# ME433_Spring2017.net
KiCad netlist of a schematic drawn in EAGLE
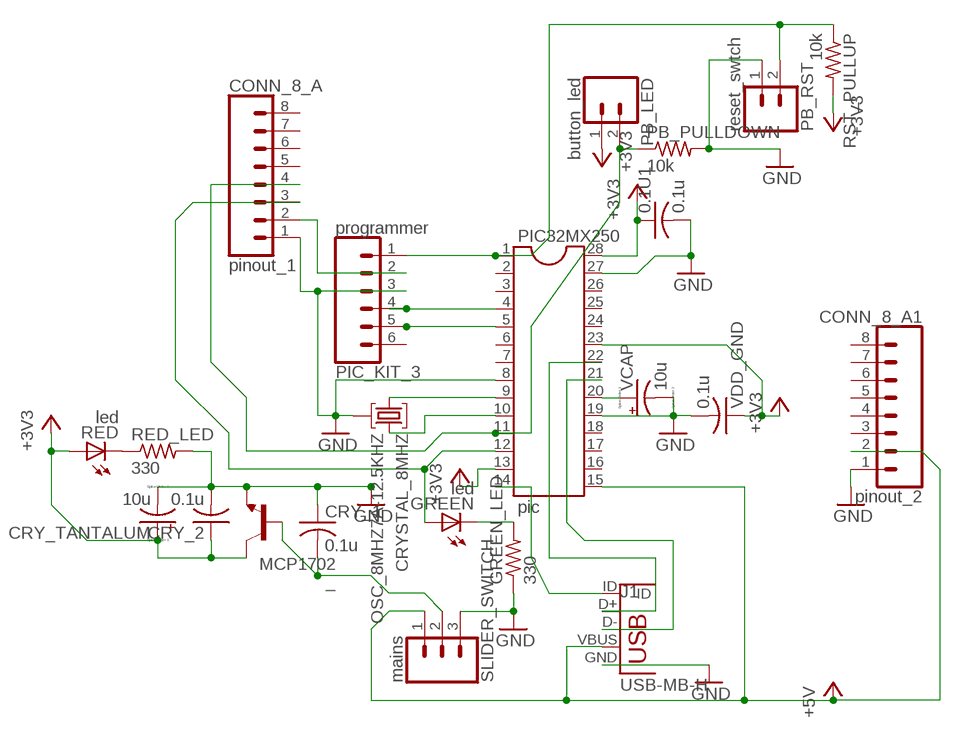
[diagram p0: schematic, sheet 1]

(export (version "E")
  (design (tool "Eeschema 10.0.6"))
  (components
    (comp (ref "0.1U1")
      (value "0.1u")
      (footprint "eagle-import:C025-025X050")
      (libsource (lib "eagle-import") (part "C-US025-025X050"))
    )
    (comp (ref "CONN_8_A")
      (value "pinout_1")
      (footprint "eagle-import:1X08")
      (libsource (lib "eagle-import") (part "CONN_08{dblquote}"))
    )
    (comp (ref "CONN_8_A1")
      (value "pinout_2")
      (footprint "eagle-import:1X08")
      (libsource (lib "eagle-import") (part "CONN_08{dblquote}"))
    )
    (comp (ref "CRYSTAL_8MHZ")
      (value "OSC_8MHZ7A-12.5KHZ")
      (footprint "eagle-import:HC49U")
      (libsource (lib "eagle-import") (part "OSC_8MHZ7A-12.5KHZ"))
    )
    (comp (ref "CRY_1")
      (value "0.1u")
      (footprint "eagle-import:C025-025X050")
      (libsource (lib "eagle-import") (part "C-US025-025X050"))
    )
    (comp (ref "CRY_2")
      (value "0.1u")
      (footprint "eagle-import:C025-025X050")
      (libsource (lib "eagle-import") (part "C-US025-025X050"))
    )
    (comp (ref "CRY_TANTALUM")
      (value "10u")
      (footprint "eagle-import:B45181B")
      (libsource (lib "eagle-import") (part "CPOL-USB45181B"))
    )
    (comp (ref "GREEN")
      (value "led")
      (footprint "eagle-import:SFH482")
      (libsource (lib "eagle-import") (part "LEDSFH482"))
    )
    (comp (ref "GREEN_LED")
      (value "330")
      (footprint "eagle-import:0204_7")
      (libsource (lib "eagle-import") (part "R-US_0204/7"))
    )
    (comp (ref "J1")
      (value "USB-MB-H")
      (footprint "eagle-import:USB-MB-H")
      (libsource (lib "eagle-import") (part "USB-MB-H"))
    )
    (comp (ref "PB_LED")
      (value "button_led")
      (footprint "eagle-import:BUTTONS")
      (libsource (lib "eagle-import") (part "BUTTONS"))
    )
    (comp (ref "PB_PULLDOWN")
      (value "10k")
      (footprint "eagle-import:0204_7")
      (libsource (lib "eagle-import") (part "R-US_0204/7"))
    )
    (comp (ref "PB_RST")
      (value "reset_swtch")
      (footprint "eagle-import:BUTTONS")
      (libsource (lib "eagle-import") (part "BUTTONS"))
    )
    (comp (ref "PIC32MX250")
      (value "pic")
      (footprint "eagle-import:PIC")
      (libsource (lib "eagle-import") (part "PIC-3"))
    )
    (comp (ref "PIC_KIT_3")
      (value "programmer")
      (footprint "eagle-import:1X06_NO_SILK")
      (libsource (lib "eagle-import") (part "PICKIT3NO_SILK_FEMALE_PTH"))
    )
    (comp (ref "RED")
      (value "led")
      (footprint "eagle-import:SFH482")
      (libsource (lib "eagle-import") (part "LEDSFH482"))
    )
    (comp (ref "RED_LED")
      (value "330")
      (footprint "eagle-import:0204_7")
      (libsource (lib "eagle-import") (part "R-US_0204/7"))
    )
    (comp (ref "RST_PULLUP")
      (value "10k")
      (footprint "eagle-import:0204_7")
      (libsource (lib "eagle-import") (part "R-US_0204/7"))
    )
    (comp (ref "SLIDER_SWITCH")
      (value "mains")
      (footprint "eagle-import:SLIDER_SWITCH_1MM")
      (libsource (lib "eagle-import") (part "SLIDER_SWITCH"))
    )
    (comp (ref "VCAP")
      (value "10u")
      (footprint "eagle-import:B45181B")
      (libsource (lib "eagle-import") (part "CPOL-USB45181B"))
    )
    (comp (ref "VDD_GND")
      (value "0.1u")
      (footprint "eagle-import:C025-025X050")
      (libsource (lib "eagle-import") (part "C-US025-025X050"))
    )
    (comp (ref "_")
      (value "MCP1702")
      (footprint "eagle-import:MCP1702")
      (libsource (lib "eagle-import") (part "MCP1702"))
    )
  )
  (nets
    (net (code "1") (name "+3V3") (class "Default")
      (node (ref "0.1U1") (pin "1") (pinfunction "1_1") (pintype "passive"))
      (node (ref "CRY_2") (pin "1") (pinfunction "1_1") (pintype "passive"))
      (node (ref "CRY_TANTALUM") (pin "+") (pinfunction "+_+") (pintype "passive"))
      (node (ref "PB_LED") (pin "1") (pinfunction "1_1") (pintype "passive"))
      (node (ref "PIC32MX250") (pin "13") (pinfunction "13_13") (pintype "passive"))
      (node (ref "PIC32MX250") (pin "23") (pinfunction "23_23") (pintype "passive"))
      (node (ref "PIC32MX250") (pin "28") (pinfunction "28_28") (pintype "passive"))
      (node (ref "RED") (pin "A") (pinfunction "A_A") (pintype "passive"))
      (node (ref "RST_PULLUP") (pin "2") (pinfunction "2_2") (pintype "passive"))
      (node (ref "VDD_GND") (pin "1") (pinfunction "1_1") (pintype "passive"))
      (node (ref "_") (pin "C") (pinfunction "C_C") (pintype "passive"))
    )
    (net (code "2") (name "+5V") (class "Default")
      (node (ref "CONN_8_A1") (pin "2") (pinfunction "2_2") (pintype "passive"))
      (node (ref "J1") (pin "VBUS") (pinfunction "VBUS_VBUS") (pintype "bidirectional"))
      (node (ref "PIC32MX250") (pin "15") (pinfunction "15_15") (pintype "passive"))
      (node (ref "SLIDER_SWITCH") (pin "1") (pinfunction "1_1") (pintype "passive"))
    )
    (net (code "3") (name "GND") (class "Default")
      (node (ref "0.1U1") (pin "2") (pinfunction "2_2") (pintype "passive"))
      (node (ref "CONN_8_A") (pin "1") (pinfunction "1_1") (pintype "passive"))
      (node (ref "CONN_8_A1") (pin "1") (pinfunction "1_1") (pintype "passive"))
      (node (ref "CRYSTAL_8MHZ") (pin "2") (pinfunction "2_2") (pintype "passive"))
      (node (ref "CRY_1") (pin "1") (pinfunction "1_1") (pintype "passive"))
      (node (ref "CRY_2") (pin "2") (pinfunction "2_2") (pintype "passive"))
      (node (ref "CRY_TANTALUM") (pin "-") (pinfunction "-_-") (pintype "passive"))
      (node (ref "GREEN_LED") (pin "1") (pinfunction "1_1") (pintype "passive"))
      (node (ref "J1") (pin "GND") (pinfunction "GND_GND") (pintype "bidirectional"))
      (node (ref "PB_PULLDOWN") (pin "2") (pinfunction "2_2") (pintype "passive"))
      (node (ref "PB_RST") (pin "1") (pinfunction "1_1") (pintype "passive"))
      (node (ref "PIC32MX250") (pin "19") (pinfunction "19_19") (pintype "passive"))
      (node (ref "PIC32MX250") (pin "27") (pinfunction "27_27") (pintype "passive"))
      (node (ref "PIC32MX250") (pin "8") (pinfunction "8_8") (pintype "passive"))
      (node (ref "PIC_KIT_3") (pin "3") (pinfunction "3_3") (pintype "passive"))
      (node (ref "RED_LED") (pin "2") (pinfunction "2_2") (pintype "passive"))
      (node (ref "SLIDER_SWITCH") (pin "3") (pinfunction "3_3") (pintype "passive"))
      (node (ref "VCAP") (pin "-") (pinfunction "-_-") (pintype "passive"))
      (node (ref "VDD_GND") (pin "2") (pinfunction "2_2") (pintype "passive"))
      (node (ref "_") (pin "E") (pinfunction "E_E") (pintype "passive"))
    )
    (net (code "4") (name "Net-(CONN_8_A-Pad2)") (class "Default")
      (node (ref "CONN_8_A") (pin "2") (pinfunction "2_2") (pintype "passive"))
      (node (ref "PIC_KIT_3") (pin "2") (pinfunction "2_2") (pintype "passive"))
    )
    (net (code "5") (name "Net-(CONN_8_A-Pad3)") (class "Default")
      (node (ref "CONN_8_A") (pin "3") (pinfunction "3_3") (pintype "passive"))
      (node (ref "GREEN") (pin "A") (pinfunction "A_A") (pintype "passive"))
      (node (ref "PIC32MX250") (pin "12") (pinfunction "12_12") (pintype "passive"))
    )
    (net (code "6") (name "Net-(CONN_8_A-Pad4)") (class "Default")
      (node (ref "CONN_8_A") (pin "4") (pinfunction "4_4") (pintype "passive"))
      (node (ref "PB_LED") (pin "2") (pinfunction "2_2") (pintype "passive"))
      (node (ref "PB_PULLDOWN") (pin "1") (pinfunction "1_1") (pintype "passive"))
      (node (ref "PIC32MX250") (pin "11") (pinfunction "11_11") (pintype "passive"))
    )
    (net (code "7") (name "Net-(CRYSTAL_8MHZ-Pad1)") (class "Default")
      (node (ref "CRYSTAL_8MHZ") (pin "1") (pinfunction "1_1") (pintype "passive"))
      (node (ref "PIC32MX250") (pin "9") (pinfunction "9_9") (pintype "passive"))
    )
    (net (code "8") (name "Net-(CRYSTAL_8MHZ-Pad3)") (class "Default")
      (node (ref "CRYSTAL_8MHZ") (pin "3") (pinfunction "3_3") (pintype "passive"))
      (node (ref "PIC32MX250") (pin "10") (pinfunction "10_10") (pintype "passive"))
    )
    (net (code "9") (name "Net-(CRY_1-Pad2)") (class "Default")
      (node (ref "CRY_1") (pin "2") (pinfunction "2_2") (pintype "passive"))
      (node (ref "SLIDER_SWITCH") (pin "2") (pinfunction "2_2") (pintype "passive"))
      (node (ref "_") (pin "B") (pinfunction "B_B") (pintype "passive"))
    )
    (net (code "10") (name "Net-(GREEN-C)") (class "Default")
      (node (ref "GREEN") (pin "K") (pinfunction "C_K") (pintype "passive"))
      (node (ref "GREEN_LED") (pin "2") (pinfunction "2_2") (pintype "passive"))
    )
    (net (code "11") (name "Net-(J1-PadD+)") (class "Default")
      (node (ref "J1") (pin "D+") (pinfunction "D+_D+") (pintype "bidirectional"))
      (node (ref "PIC32MX250") (pin "22") (pinfunction "22_22") (pintype "passive"))
    )
    (net (code "12") (name "Net-(J1-PadD-)") (class "Default")
      (node (ref "J1") (pin "D-") (pinfunction "D-_D-") (pintype "bidirectional"))
      (node (ref "PIC32MX250") (pin "21") (pinfunction "21_21") (pintype "passive"))
    )
    (net (code "13") (name "Net-(J1-PadID)") (class "Default")
      (node (ref "J1") (pin "ID") (pinfunction "ID_ID") (pintype "bidirectional"))
      (node (ref "PIC32MX250") (pin "14") (pinfunction "14_14") (pintype "passive"))
    )
    (net (code "14") (name "Net-(PB_RST-Pad2)") (class "Default")
      (node (ref "PB_RST") (pin "2") (pinfunction "2_2") (pintype "passive"))
      (node (ref "PIC32MX250") (pin "1") (pinfunction "1_1") (pintype "passive"))
      (node (ref "PIC_KIT_3") (pin "1") (pinfunction "1_1") (pintype "passive"))
      (node (ref "RST_PULLUP") (pin "1") (pinfunction "1_1") (pintype "passive"))
    )
    (net (code "15") (name "Net-(PIC32MX250-Pad4)") (class "Default")
      (node (ref "PIC32MX250") (pin "4") (pinfunction "4_4") (pintype "passive"))
      (node (ref "PIC_KIT_3") (pin "4") (pinfunction "4_4") (pintype "passive"))
    )
    (net (code "16") (name "Net-(PIC32MX250-Pad5)") (class "Default")
      (node (ref "PIC32MX250") (pin "5") (pinfunction "5_5") (pintype "passive"))
      (node (ref "PIC_KIT_3") (pin "5") (pinfunction "5_5") (pintype "passive"))
    )
    (net (code "17") (name "Net-(PIC32MX250-Pad20)") (class "Default")
      (node (ref "PIC32MX250") (pin "20") (pinfunction "20_20") (pintype "passive"))
      (node (ref "VCAP") (pin "+") (pinfunction "+_+") (pintype "passive"))
    )
    (net (code "18") (name "Net-(RED-C)") (class "Default")
      (node (ref "RED") (pin "K") (pinfunction "C_K") (pintype "passive"))
      (node (ref "RED_LED") (pin "1") (pinfunction "1_1") (pintype "passive"))
    )
    (net (code "19") (name "unconnected-(CONN_8_A-Pad5)") (class "Default")
      (node (ref "CONN_8_A") (pin "5") (pinfunction "5_5") (pintype "passive"))
    )
    (net (code "20") (name "unconnected-(CONN_8_A-Pad6)") (class "Default")
      (node (ref "CONN_8_A") (pin "6") (pinfunction "6_6") (pintype "passive"))
    )
    (net (code "21") (name "unconnected-(CONN_8_A-Pad7)") (class "Default")
      (node (ref "CONN_8_A") (pin "7") (pinfunction "7_7") (pintype "passive"))
    )
    (net (code "22") (name "unconnected-(CONN_8_A-Pad8)") (class "Default")
      (node (ref "CONN_8_A") (pin "8") (pinfunction "8_8") (pintype "passive"))
    )
    (net (code "23") (name "unconnected-(CONN_8_A1-Pad3)") (class "Default")
      (node (ref "CONN_8_A1") (pin "3") (pinfunction "3_3") (pintype "passive"))
    )
    (net (code "24") (name "unconnected-(CONN_8_A1-Pad4)") (class "Default")
      (node (ref "CONN_8_A1") (pin "4") (pinfunction "4_4") (pintype "passive"))
    )
    (net (code "25") (name "unconnected-(CONN_8_A1-Pad5)") (class "Default")
      (node (ref "CONN_8_A1") (pin "5") (pinfunction "5_5") (pintype "passive"))
    )
    (net (code "26") (name "unconnected-(CONN_8_A1-Pad6)") (class "Default")
      (node (ref "CONN_8_A1") (pin "6") (pinfunction "6_6") (pintype "passive"))
    )
    (net (code "27") (name "unconnected-(CONN_8_A1-Pad7)") (class "Default")
      (node (ref "CONN_8_A1") (pin "7") (pinfunction "7_7") (pintype "passive"))
    )
    (net (code "28") (name "unconnected-(CONN_8_A1-Pad8)") (class "Default")
      (node (ref "CONN_8_A1") (pin "8") (pinfunction "8_8") (pintype "passive"))
    )
    (net (code "29") (name "unconnected-(PIC32MX250-Pad2)") (class "Default")
      (node (ref "PIC32MX250") (pin "2") (pinfunction "2_2") (pintype "passive"))
    )
    (net (code "30") (name "unconnected-(PIC32MX250-Pad3)") (class "Default")
      (node (ref "PIC32MX250") (pin "3") (pinfunction "3_3") (pintype "passive"))
    )
    (net (code "31") (name "unconnected-(PIC32MX250-Pad6)") (class "Default")
      (node (ref "PIC32MX250") (pin "6") (pinfunction "6_6") (pintype "passive"))
    )
    (net (code "32") (name "unconnected-(PIC32MX250-Pad7)") (class "Default")
      (node (ref "PIC32MX250") (pin "7") (pinfunction "7_7") (pintype "passive"))
    )
    (net (code "33") (name "unconnected-(PIC32MX250-Pad16)") (class "Default")
      (node (ref "PIC32MX250") (pin "16") (pinfunction "16_16") (pintype "passive"))
    )
    (net (code "34") (name "unconnected-(PIC32MX250-Pad17)") (class "Default")
      (node (ref "PIC32MX250") (pin "17") (pinfunction "17_17") (pintype "passive"))
    )
    (net (code "35") (name "unconnected-(PIC32MX250-Pad18)") (class "Default")
      (node (ref "PIC32MX250") (pin "18") (pinfunction "18_18") (pintype "passive"))
    )
    (net (code "36") (name "unconnected-(PIC32MX250-Pad24)") (class "Default")
      (node (ref "PIC32MX250") (pin "24") (pinfunction "24_24") (pintype "passive"))
    )
    (net (code "37") (name "unconnected-(PIC32MX250-Pad25)") (class "Default")
      (node (ref "PIC32MX250") (pin "25") (pinfunction "25_25") (pintype "passive"))
    )
    (net (code "38") (name "unconnected-(PIC32MX250-Pad26)") (class "Default")
      (node (ref "PIC32MX250") (pin "26") (pinfunction "26_26") (pintype "passive"))
    )
    (net (code "39") (name "unconnected-(PIC_KIT_3-Pad6)") (class "Default")
      (node (ref "PIC_KIT_3") (pin "6") (pinfunction "6_6") (pintype "passive"))
    )
  )
)
